# Sheet1.net
KiCad netlist of a schematic drawn in Altium Designer
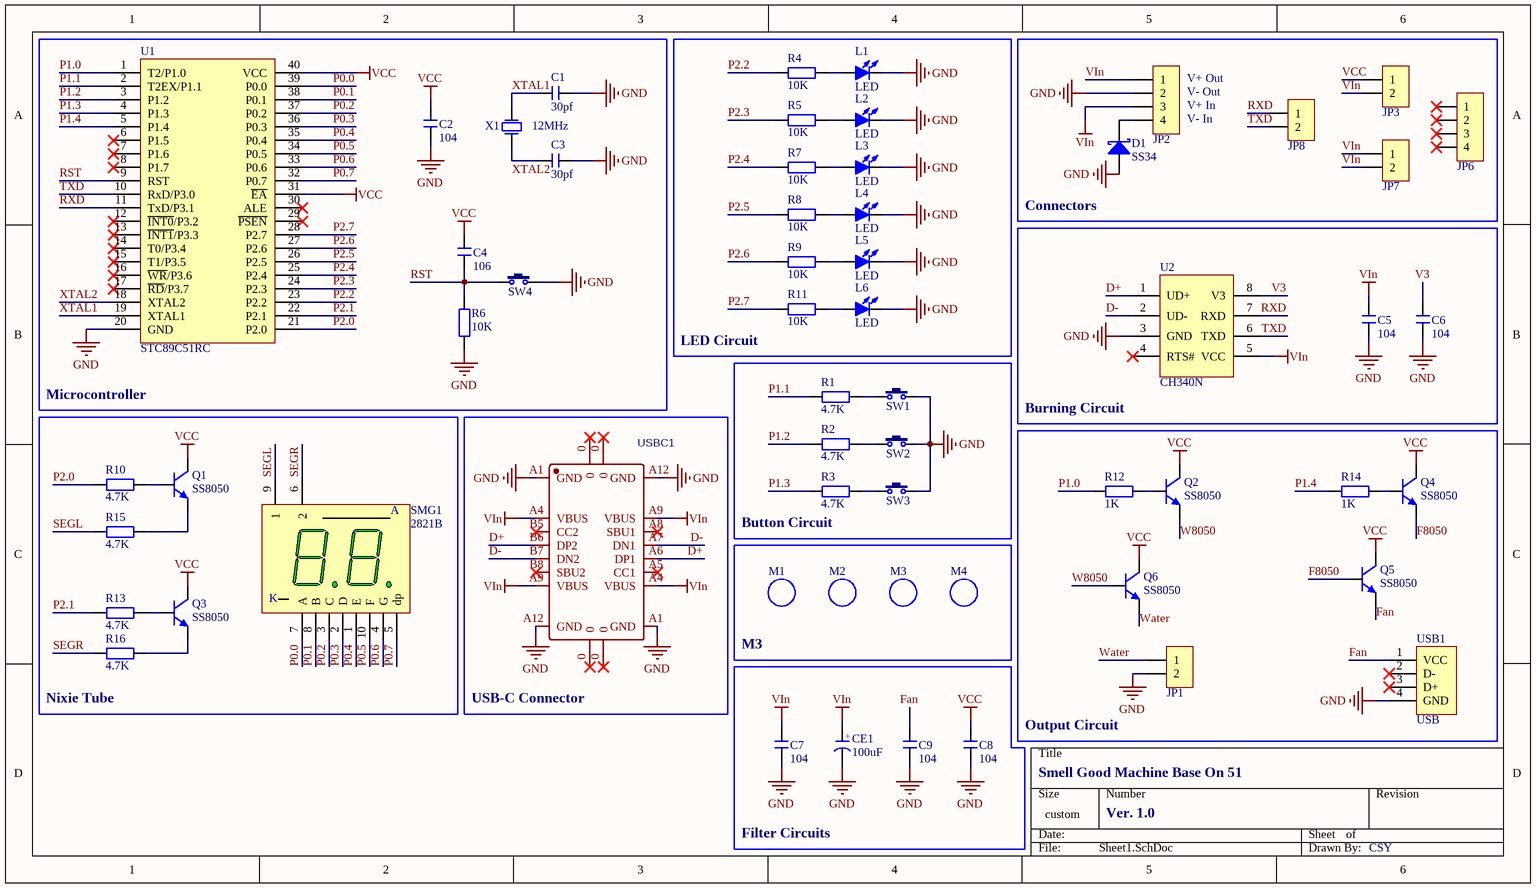
[diagram p0: Sheet1.SchDoc]

(export (version "E")
  (design (tool "Eeschema 10.0.6"))
  (components
    (comp (ref "C1")
      (value "30pf")
      (footprint "C 0805_M")
      (description "贴片电容")
      (libsource (lib "01 - 电容-电阻-电感") (part "C"))
    )
    (comp (ref "C2")
      (value "104")
      (footprint "C 0805_M")
      (description "贴片电容")
      (libsource (lib "01 - 电容-电阻-电感") (part "C"))
    )
    (comp (ref "C3")
      (value "30pf")
      (footprint "C 0805_M")
      (description "贴片电容")
      (libsource (lib "01 - 电容-电阻-电感") (part "C"))
    )
    (comp (ref "C4")
      (value "106")
      (footprint "C 0805_M")
      (description "贴片电容")
      (libsource (lib "01 - 电容-电阻-电感") (part "C"))
    )
    (comp (ref "C5")
      (value "104")
      (footprint "C 0805_M")
      (description "贴片电容")
      (libsource (lib "01 - 电容-电阻-电感") (part "C"))
    )
    (comp (ref "C6")
      (value "104")
      (footprint "C 0805_M")
      (description "贴片电容")
      (libsource (lib "01 - 电容-电阻-电感") (part "C"))
    )
    (comp (ref "C7")
      (value "104")
      (footprint "C 0805_M")
      (description "贴片电容")
      (libsource (lib "01 - 电容-电阻-电感") (part "C"))
    )
    (comp (ref "C8")
      (value "104")
      (footprint "C 0805_M")
      (description "贴片电容")
      (libsource (lib "01 - 电容-电阻-电感") (part "C"))
    )
    (comp (ref "C9")
      (value "104")
      (footprint "C 0805_M")
      (description "贴片电容")
      (libsource (lib "01 - 电容-电阻-电感") (part "C"))
    )
    (comp (ref "CE1")
      (value "100uF")
      (footprint "CM D(6.3*7.7)")
      (description "贴片电解电容")
      (libsource (lib "01 - 电容-电阻-电感") (part "CE_SMD"))
    )
    (comp (ref "D1")
      (value "SS34")
      (footprint "SMA")
      (description "肖特基二极管")
      (libsource (lib "02 - 二极管(LED)-三极管-整流桥") (part "SS34"))
    )
    (comp (ref "JP1")
      (value "HDR-1X2")
      (footprint "HDR2.54-LI-2P")
      (description "2P接插件")
      (libsource (lib "17 - 接插件-脚距2.54mm (100mil) ") (part "Header 2"))
    )
    (comp (ref "JP2")
      (value "HDR-1X4")
      (footprint "HDR2.54-LI-4P")
      (description "4P接插件")
      (libsource (lib "17 - 接插件-脚距2.54mm (100mil) ") (part "Header 4"))
    )
    (comp (ref "JP3")
      (value "HDR-1X2")
      (footprint "HDR2.54-LI-2P")
      (description "2P接插件")
      (libsource (lib "17 - 接插件-脚距2.54mm (100mil) ") (part "Header 2"))
    )
    (comp (ref "JP6")
      (value "HDR-1X4")
      (footprint "HDR2.54-LI-4P")
      (description "4P接插件")
      (libsource (lib "17 - 接插件-脚距2.54mm (100mil) ") (part "Header 4"))
    )
    (comp (ref "JP7")
      (value "HDR-1X2")
      (footprint "HDR2.54-LI-2P")
      (description "2P接插件")
      (libsource (lib "17 - 接插件-脚距2.54mm (100mil) ") (part "Header 2"))
    )
    (comp (ref "JP8")
      (value "HDR-1X2")
      (footprint "HDR2.54-LI-2P")
      (description "2P接插件")
      (libsource (lib "17 - 接插件-脚距2.54mm (100mil) ") (part "Header 2"))
    )
    (comp (ref "L1")
      (value "LED")
      (footprint "LED 0805B")
      (description "发光二极管")
      (libsource (lib "02 - 二极管(LED)-三极管-整流桥") (part "LED"))
    )
    (comp (ref "L2")
      (value "LED")
      (footprint "LED 0805R")
      (description "发光二极管")
      (libsource (lib "02 - 二极管(LED)-三极管-整流桥") (part "LED"))
    )
    (comp (ref "L3")
      (value "LED")
      (footprint "LED 0805R")
      (description "发光二极管")
      (libsource (lib "02 - 二极管(LED)-三极管-整流桥") (part "LED"))
    )
    (comp (ref "L4")
      (value "LED")
      (footprint "LED 0805R")
      (description "发光二极管")
      (libsource (lib "02 - 二极管(LED)-三极管-整流桥") (part "LED"))
    )
    (comp (ref "L5")
      (value "LED")
      (footprint "LED 0805R")
      (description "发光二极管")
      (libsource (lib "02 - 二极管(LED)-三极管-整流桥") (part "LED"))
    )
    (comp (ref "L6")
      (value "LED")
      (footprint "LED 0805G")
      (description "发光二极管")
      (libsource (lib "02 - 二极管(LED)-三极管-整流桥") (part "LED"))
    )
    (comp (ref "M1")
      (value "M3")
      (footprint "M3x20_N")
      (description "铜柱孔")
      (libsource (lib "10 - 未分类元器件") (part "M3"))
    )
    (comp (ref "M2")
      (value "M3")
      (footprint "M3x20_N")
      (description "铜柱孔")
      (libsource (lib "10 - 未分类元器件") (part "M3"))
    )
    (comp (ref "M3")
      (value "M3")
      (footprint "M3x20_N")
      (description "铜柱孔")
      (libsource (lib "10 - 未分类元器件") (part "M3"))
    )
    (comp (ref "M4")
      (value "M3")
      (footprint "M3x20_N")
      (description "铜柱孔")
      (libsource (lib "10 - 未分类元器件") (part "M3"))
    )
    (comp (ref "Q1")
      (value "SS8050")
      (footprint "SOT23-3M")
      (description "高频放大-NPN型")
      (libsource (lib "02 - 二极管(LED)-三极管-整流桥") (part "8050-SMD"))
    )
    (comp (ref "Q2")
      (value "SS8050")
      (footprint "SOT23-3M")
      (description "高频放大-NPN型")
      (libsource (lib "02 - 二极管(LED)-三极管-整流桥") (part "8050-SMD"))
    )
    (comp (ref "Q3")
      (value "SS8050")
      (footprint "SOT23-3M")
      (description "高频放大-NPN型")
      (libsource (lib "02 - 二极管(LED)-三极管-整流桥") (part "8050-SMD"))
    )
    (comp (ref "Q4")
      (value "SS8050")
      (footprint "SOT23-3M")
      (description "高频放大-NPN型")
      (libsource (lib "02 - 二极管(LED)-三极管-整流桥") (part "8050-SMD"))
    )
    (comp (ref "Q5")
      (value "SS8050")
      (footprint "SOT23-3M")
      (description "高频放大-NPN型")
      (libsource (lib "02 - 二极管(LED)-三极管-整流桥") (part "8050-SMD"))
    )
    (comp (ref "Q6")
      (value "SS8050")
      (footprint "SOT23-3M")
      (description "高频放大-NPN型")
      (libsource (lib "02 - 二极管(LED)-三极管-整流桥") (part "8050-SMD"))
    )
    (comp (ref "R1")
      (value "4.7K")
      (footprint "R 0805_M")
      (description "贴片电阻")
      (libsource (lib "01 - 电容-电阻-电感") (part "R"))
    )
    (comp (ref "R2")
      (value "4.7K")
      (footprint "R 0805_M")
      (description "贴片电阻")
      (libsource (lib "01 - 电容-电阻-电感") (part "R"))
    )
    (comp (ref "R3")
      (value "4.7K")
      (footprint "R 0805_M")
      (description "贴片电阻")
      (libsource (lib "01 - 电容-电阻-电感") (part "R"))
    )
    (comp (ref "R4")
      (value "10K")
      (footprint "R 0805_M")
      (description "贴片电阻")
      (libsource (lib "01 - 电容-电阻-电感") (part "R"))
    )
    (comp (ref "R5")
      (value "10K")
      (footprint "R 0805_M")
      (description "贴片电阻")
      (libsource (lib "01 - 电容-电阻-电感") (part "R"))
    )
    (comp (ref "R6")
      (value "10K")
      (footprint "R 0805_M")
      (description "贴片电阻")
      (libsource (lib "01 - 电容-电阻-电感") (part "R"))
    )
    (comp (ref "R7")
      (value "10K")
      (footprint "R 0805_M")
      (description "贴片电阻")
      (libsource (lib "01 - 电容-电阻-电感") (part "R"))
    )
    (comp (ref "R8")
      (value "10K")
      (footprint "R 0805_M")
      (description "贴片电阻")
      (libsource (lib "01 - 电容-电阻-电感") (part "R"))
    )
    (comp (ref "R9")
      (value "10K")
      (footprint "R 0805_M")
      (description "贴片电阻")
      (libsource (lib "01 - 电容-电阻-电感") (part "R"))
    )
    (comp (ref "R10")
      (value "4.7K")
      (footprint "R 0805_M")
      (description "贴片电阻")
      (libsource (lib "01 - 电容-电阻-电感") (part "R"))
    )
    (comp (ref "R11")
      (value "10K")
      (footprint "R 0805_M")
      (description "贴片电阻")
      (libsource (lib "01 - 电容-电阻-电感") (part "R"))
    )
    (comp (ref "R12")
      (value "1K")
      (footprint "R 0805_M")
      (description "贴片电阻")
      (libsource (lib "01 - 电容-电阻-电感") (part "R"))
    )
    (comp (ref "R13")
      (value "4.7K")
      (footprint "R 0805_M")
      (description "贴片电阻")
      (libsource (lib "01 - 电容-电阻-电感") (part "R"))
    )
    (comp (ref "R14")
      (value "1K")
      (footprint "R 0805_M")
      (description "贴片电阻")
      (libsource (lib "01 - 电容-电阻-电感") (part "R"))
    )
    (comp (ref "R15")
      (value "4.7K")
      (footprint "R 0805_M")
      (description "贴片电阻")
      (libsource (lib "01 - 电容-电阻-电感") (part "R"))
    )
    (comp (ref "R16")
      (value "4.7K")
      (footprint "R 0805_M")
      (description "贴片电阻")
      (libsource (lib "01 - 电容-电阻-电感") (part "R"))
    )
    (comp (ref "SMG1")
      (value "2821B")
      (footprint "SMG 0.28-2P")
      (description "0.28寸2位共阳数码管")
      (libsource (lib "05 - 点阵-液晶-数码管-TFT") (part "2821B"))
    )
    (comp (ref "SW1")
      (value "3x6x5")
      (footprint "TSW SMD-3*6*2.5")
      (description "3x6轻触开关")
      (libsource (lib "03 - 按键-开关-晶振-蜂鸣器") (part "TSW 3x6"))
    )
    (comp (ref "SW2")
      (value "3x6x5")
      (footprint "TSW SMD-3*6*2.5")
      (description "3x6轻触开关")
      (libsource (lib "03 - 按键-开关-晶振-蜂鸣器") (part "TSW 3x6"))
    )
    (comp (ref "SW3")
      (value "3x6x5")
      (footprint "TSW SMD-3*6*2.5")
      (description "3x6轻触开关")
      (libsource (lib "03 - 按键-开关-晶振-蜂鸣器") (part "TSW 3x6"))
    )
    (comp (ref "SW4")
      (value "3x6x5")
      (footprint "TSW SMD-3*6*2.5")
      (description "3x6轻触开关")
      (libsource (lib "03 - 按键-开关-晶振-蜂鸣器") (part "TSW 3x6"))
    )
    (comp (ref "U1")
      (value "STC89C51RC")
      (footprint "DIP40-600_MH")
      (description "STC单片机")
      (libsource (lib "25 - STC系列单片机") (part "STC89C51RC"))
    )
    (comp (ref "U2")
      (value "CH340N")
      (footprint "SOP8_M")
      (description "CH340N/CH330N")
      (libsource (lib "Schlib1") (part "CH340N"))
    )
    (comp (ref "USB1")
      (value "USB")
      (footprint "USB-A/S_D")
      (description "USB-A型母接口")
      (libsource (lib "04 - 接口类-USB接口-网口") (part "USB-A/S"))
    )
    (comp (ref "USBC1")
      (value "TYPE-C-31-M-12")
      (footprint "USB-TYPE-C-R")
      (description "Type-C母座")
      (fields (field (name "BOM_SUPPLIER PART") "C165948") (field (name "CONTRIBUTOR") "LCSC"))
      (libsource (lib "Schlib1") (part "TYPE-C-31-M-12"))
    )
    (comp (ref "X1")
      (value "12MHz")
      (footprint "OSC HC-49SMD")
      (description "2脚无源脚晶振")
      (libsource (lib "03 - 按键-开关-晶振-蜂鸣器") (part "XTAL-2P"))
    )
  )
  (nets
    (net (code "1") (name "/D+") (class "Default")
      (node (ref "U2") (pin "1") (pinfunction "UD+_1") (pintype "passive"))
      (node (ref "USBC1") (pin "A6") (pinfunction "DP1_A6") (pintype "passive"))
      (node (ref "USBC1") (pin "B6") (pinfunction "DP2_B6") (pintype "passive"))
    )
    (net (code "2") (name "/D-") (class "Default")
      (node (ref "U2") (pin "2") (pinfunction "UD-_2") (pintype "passive"))
      (node (ref "USBC1") (pin "A7") (pinfunction "DN1_A7") (pintype "passive"))
      (node (ref "USBC1") (pin "B7") (pinfunction "DN2_B7") (pintype "passive"))
    )
    (net (code "3") (name "/F8050") (class "Default")
      (node (ref "Q4") (pin "2") (pinfunction "E_2") (pintype "passive"))
      (node (ref "Q5") (pin "1") (pinfunction "B_1") (pintype "passive"))
    )
    (net (code "4") (name "/Fan") (class "Default")
      (node (ref "C9") (pin "2") (pinfunction "2_2") (pintype "passive"))
      (node (ref "Q5") (pin "2") (pinfunction "E_2") (pintype "passive"))
      (node (ref "USB1") (pin "1") (pinfunction "VCC_1") (pintype "passive"))
    )
    (net (code "5") (name "/P0.0") (class "Default")
      (node (ref "SMG1") (pin "7") (pinfunction "A_7") (pintype "passive"))
      (node (ref "U1") (pin "39") (pinfunction "P0.0_39") (pintype "passive"))
    )
    (net (code "6") (name "/P0.1") (class "Default")
      (node (ref "SMG1") (pin "8") (pinfunction "B_8") (pintype "passive"))
      (node (ref "U1") (pin "38") (pinfunction "P0.1_38") (pintype "passive"))
    )
    (net (code "7") (name "/P0.2") (class "Default")
      (node (ref "SMG1") (pin "3") (pinfunction "C_3") (pintype "passive"))
      (node (ref "U1") (pin "37") (pinfunction "P0.2_37") (pintype "passive"))
    )
    (net (code "8") (name "/P0.3") (class "Default")
      (node (ref "SMG1") (pin "2") (pinfunction "D_2") (pintype "passive"))
      (node (ref "U1") (pin "36") (pinfunction "P0.3_36") (pintype "passive"))
    )
    (net (code "9") (name "/P0.4") (class "Default")
      (node (ref "SMG1") (pin "1") (pinfunction "E_1") (pintype "passive"))
      (node (ref "U1") (pin "35") (pinfunction "P0.4_35") (pintype "passive"))
    )
    (net (code "10") (name "/P0.5") (class "Default")
      (node (ref "SMG1") (pin "10") (pinfunction "F_10") (pintype "passive"))
      (node (ref "U1") (pin "34") (pinfunction "P0.5_34") (pintype "passive"))
    )
    (net (code "11") (name "/P0.6") (class "Default")
      (node (ref "SMG1") (pin "4") (pinfunction "G_4") (pintype "passive"))
      (node (ref "U1") (pin "33") (pinfunction "P0.6_33") (pintype "passive"))
    )
    (net (code "12") (name "/P0.7") (class "Default")
      (node (ref "SMG1") (pin "5") (pinfunction "dp_5") (pintype "passive"))
      (node (ref "U1") (pin "32") (pinfunction "P0.7_32") (pintype "passive"))
    )
    (net (code "13") (name "/P1.0") (class "Default")
      (node (ref "R12") (pin "2") (pinfunction "2_2") (pintype "passive"))
      (node (ref "U1") (pin "1") (pinfunction "T2/P1.0_1") (pintype "passive"))
    )
    (net (code "14") (name "/P1.1") (class "Default")
      (node (ref "R1") (pin "2") (pinfunction "2_2") (pintype "passive"))
      (node (ref "U1") (pin "2") (pinfunction "T2EX/P1.1_2") (pintype "passive"))
    )
    (net (code "15") (name "/P1.2") (class "Default")
      (node (ref "R2") (pin "2") (pinfunction "2_2") (pintype "passive"))
      (node (ref "U1") (pin "3") (pinfunction "P1.2_3") (pintype "passive"))
    )
    (net (code "16") (name "/P1.3") (class "Default")
      (node (ref "R3") (pin "2") (pinfunction "2_2") (pintype "passive"))
      (node (ref "U1") (pin "4") (pinfunction "P1.3_4") (pintype "passive"))
    )
    (net (code "17") (name "/P1.4") (class "Default")
      (node (ref "R14") (pin "2") (pinfunction "2_2") (pintype "passive"))
      (node (ref "U1") (pin "5") (pinfunction "P1.4_5") (pintype "passive"))
    )
    (net (code "18") (name "/P2.0") (class "Default")
      (node (ref "R10") (pin "2") (pinfunction "2_2") (pintype "passive"))
      (node (ref "U1") (pin "21") (pinfunction "P2.0_21") (pintype "passive"))
    )
    (net (code "19") (name "/P2.1") (class "Default")
      (node (ref "R13") (pin "2") (pinfunction "2_2") (pintype "passive"))
      (node (ref "U1") (pin "22") (pinfunction "P2.1_22") (pintype "passive"))
    )
    (net (code "20") (name "/P2.2") (class "Default")
      (node (ref "R4") (pin "2") (pinfunction "2_2") (pintype "passive"))
      (node (ref "U1") (pin "23") (pinfunction "P2.2_23") (pintype "passive"))
    )
    (net (code "21") (name "/P2.3") (class "Default")
      (node (ref "R5") (pin "2") (pinfunction "2_2") (pintype "passive"))
      (node (ref "U1") (pin "24") (pinfunction "P2.3_24") (pintype "passive"))
    )
    (net (code "22") (name "/P2.4") (class "Default")
      (node (ref "R7") (pin "2") (pinfunction "2_2") (pintype "passive"))
      (node (ref "U1") (pin "25") (pinfunction "P2.4_25") (pintype "passive"))
    )
    (net (code "23") (name "/P2.5") (class "Default")
      (node (ref "R8") (pin "2") (pinfunction "2_2") (pintype "passive"))
      (node (ref "U1") (pin "26") (pinfunction "P2.5_26") (pintype "passive"))
    )
    (net (code "24") (name "/P2.6") (class "Default")
      (node (ref "R9") (pin "2") (pinfunction "2_2") (pintype "passive"))
      (node (ref "U1") (pin "27") (pinfunction "P2.6_27") (pintype "passive"))
    )
    (net (code "25") (name "/P2.7") (class "Default")
      (node (ref "R11") (pin "2") (pinfunction "2_2") (pintype "passive"))
      (node (ref "U1") (pin "28") (pinfunction "P2.7_28") (pintype "passive"))
    )
    (net (code "26") (name "/RST") (class "Default")
      (node (ref "C4") (pin "1") (pinfunction "1_1") (pintype "passive"))
      (node (ref "R6") (pin "2") (pinfunction "2_2") (pintype "passive"))
      (node (ref "SW4") (pin "1") (pinfunction "1_1") (pintype "passive"))
      (node (ref "U1") (pin "9") (pinfunction "RST_9") (pintype "passive"))
    )
    (net (code "27") (name "/RXD") (class "Default")
      (node (ref "JP8") (pin "1") (pinfunction "1_1") (pintype "passive"))
      (node (ref "U1") (pin "11") (pinfunction "TxD/P3.1_11") (pintype "passive"))
      (node (ref "U2") (pin "7") (pinfunction "RXD_7") (pintype "passive"))
    )
    (net (code "28") (name "/SEGL") (class "Default")
      (node (ref "R15") (pin "2") (pinfunction "2_2") (pintype "passive"))
      (node (ref "SMG1") (pin "9") (pinfunction "1_9") (pintype "passive"))
    )
    (net (code "29") (name "/SEGR") (class "Default")
      (node (ref "R16") (pin "2") (pinfunction "2_2") (pintype "passive"))
      (node (ref "SMG1") (pin "6") (pinfunction "2_6") (pintype "passive"))
    )
    (net (code "30") (name "/TXD") (class "Default")
      (node (ref "JP8") (pin "2") (pinfunction "2_2") (pintype "passive"))
      (node (ref "U1") (pin "10") (pinfunction "RxD/P3.0_10") (pintype "passive"))
      (node (ref "U2") (pin "6") (pinfunction "TXD_6") (pintype "passive"))
    )
    (net (code "31") (name "/V3") (class "Default")
      (node (ref "C6") (pin "2") (pinfunction "2_2") (pintype "passive"))
      (node (ref "U2") (pin "8") (pinfunction "V3_8") (pintype "passive"))
    )
    (net (code "32") (name "/W8050") (class "Default")
      (node (ref "Q2") (pin "2") (pinfunction "E_2") (pintype "passive"))
      (node (ref "Q6") (pin "1") (pinfunction "B_1") (pintype "passive"))
    )
    (net (code "33") (name "/Water") (class "Default")
      (node (ref "JP1") (pin "1") (pinfunction "1_1") (pintype "passive"))
      (node (ref "Q6") (pin "2") (pinfunction "E_2") (pintype "passive"))
    )
    (net (code "34") (name "/XTAL1") (class "Default")
      (node (ref "C1") (pin "1") (pinfunction "1_1") (pintype "passive"))
      (node (ref "U1") (pin "19") (pinfunction "XTAL1_19") (pintype "passive"))
      (node (ref "X1") (pin "2") (pinfunction "2_2") (pintype "passive"))
    )
    (net (code "35") (name "/XTAL2") (class "Default")
      (node (ref "C3") (pin "1") (pinfunction "1_1") (pintype "passive"))
      (node (ref "U1") (pin "18") (pinfunction "XTAL2_18") (pintype "passive"))
      (node (ref "X1") (pin "1") (pinfunction "1_1") (pintype "passive"))
    )
    (net (code "36") (name "GND") (class "Default")
      (node (ref "C1") (pin "2") (pinfunction "2_2") (pintype "passive"))
      (node (ref "C2") (pin "1") (pinfunction "1_1") (pintype "passive"))
      (node (ref "C3") (pin "2") (pinfunction "2_2") (pintype "passive"))
      (node (ref "C5") (pin "1") (pinfunction "1_1") (pintype "passive"))
      (node (ref "C6") (pin "1") (pinfunction "1_1") (pintype "passive"))
      (node (ref "C7") (pin "1") (pinfunction "1_1") (pintype "passive"))
      (node (ref "C8") (pin "1") (pinfunction "1_1") (pintype "passive"))
      (node (ref "C9") (pin "1") (pinfunction "1_1") (pintype "passive"))
      (node (ref "CE1") (pin "2") (pinfunction "K_2") (pintype "passive"))
      (node (ref "D1") (pin "1") (pinfunction "A_1") (pintype "passive"))
      (node (ref "JP1") (pin "2") (pinfunction "2_2") (pintype "passive"))
      (node (ref "JP2") (pin "2") (pinfunction "2_2") (pintype "passive"))
      (node (ref "L1") (pin "2") (pinfunction "K_2") (pintype "passive"))
      (node (ref "L2") (pin "2") (pinfunction "K_2") (pintype "passive"))
      (node (ref "L3") (pin "2") (pinfunction "K_2") (pintype "passive"))
      (node (ref "L4") (pin "2") (pinfunction "K_2") (pintype "passive"))
      (node (ref "L5") (pin "2") (pinfunction "K_2") (pintype "passive"))
      (node (ref "L6") (pin "2") (pinfunction "K_2") (pintype "passive"))
      (node (ref "R6") (pin "1") (pinfunction "1_1") (pintype "passive"))
      (node (ref "SW1") (pin "2") (pinfunction "2_2") (pintype "passive"))
      (node (ref "SW2") (pin "2") (pinfunction "2_2") (pintype "passive"))
      (node (ref "SW3") (pin "2") (pinfunction "2_2") (pintype "passive"))
      (node (ref "SW4") (pin "2") (pinfunction "2_2") (pintype "passive"))
      (node (ref "U1") (pin "20") (pinfunction "GND_20") (pintype "passive"))
      (node (ref "U2") (pin "3") (pinfunction "GND_3") (pintype "passive"))
      (node (ref "USB1") (pin "4") (pinfunction "GND_4") (pintype "passive"))
      (node (ref "USBC1") (pin "A1") (pinfunction "GND_A1") (pintype "passive"))
      (node (ref "USBC1") (pin "A12") (pinfunction "GND_A12") (pintype "passive"))
    )
    (net (code "37") (name "Net-(D1-K)") (class "Default")
      (node (ref "D1") (pin "2") (pinfunction "K_2") (pintype "passive"))
      (node (ref "JP2") (pin "4") (pinfunction "4_4") (pintype "passive"))
    )
    (net (code "38") (name "Net-(L1-A)") (class "Default")
      (node (ref "L1") (pin "1") (pinfunction "A_1") (pintype "passive"))
      (node (ref "R4") (pin "1") (pinfunction "1_1") (pintype "passive"))
    )
    (net (code "39") (name "Net-(L2-A)") (class "Default")
      (node (ref "L2") (pin "1") (pinfunction "A_1") (pintype "passive"))
      (node (ref "R5") (pin "1") (pinfunction "1_1") (pintype "passive"))
    )
    (net (code "40") (name "Net-(L3-A)") (class "Default")
      (node (ref "L3") (pin "1") (pinfunction "A_1") (pintype "passive"))
      (node (ref "R7") (pin "1") (pinfunction "1_1") (pintype "passive"))
    )
    (net (code "41") (name "Net-(L4-A)") (class "Default")
      (node (ref "L4") (pin "1") (pinfunction "A_1") (pintype "passive"))
      (node (ref "R8") (pin "1") (pinfunction "1_1") (pintype "passive"))
    )
    (net (code "42") (name "Net-(L5-A)") (class "Default")
      (node (ref "L5") (pin "1") (pinfunction "A_1") (pintype "passive"))
      (node (ref "R9") (pin "1") (pinfunction "1_1") (pintype "passive"))
    )
    (net (code "43") (name "Net-(L6-A)") (class "Default")
      (node (ref "L6") (pin "1") (pinfunction "A_1") (pintype "passive"))
      (node (ref "R11") (pin "1") (pinfunction "1_1") (pintype "passive"))
    )
    (net (code "44") (name "Net-(Q1-B)") (class "Default")
      (node (ref "Q1") (pin "1") (pinfunction "B_1") (pintype "passive"))
      (node (ref "R10") (pin "1") (pinfunction "1_1") (pintype "passive"))
    )
    (net (code "45") (name "Net-(Q1-E)") (class "Default")
      (node (ref "Q1") (pin "2") (pinfunction "E_2") (pintype "passive"))
      (node (ref "R15") (pin "1") (pinfunction "1_1") (pintype "passive"))
    )
    (net (code "46") (name "Net-(Q2-B)") (class "Default")
      (node (ref "Q2") (pin "1") (pinfunction "B_1") (pintype "passive"))
      (node (ref "R12") (pin "1") (pinfunction "1_1") (pintype "passive"))
    )
    (net (code "47") (name "Net-(Q3-B)") (class "Default")
      (node (ref "Q3") (pin "1") (pinfunction "B_1") (pintype "passive"))
      (node (ref "R13") (pin "1") (pinfunction "1_1") (pintype "passive"))
    )
    (net (code "48") (name "Net-(Q3-E)") (class "Default")
      (node (ref "Q3") (pin "2") (pinfunction "E_2") (pintype "passive"))
      (node (ref "R16") (pin "1") (pinfunction "1_1") (pintype "passive"))
    )
    (net (code "49") (name "Net-(Q4-B)") (class "Default")
      (node (ref "Q4") (pin "1") (pinfunction "B_1") (pintype "passive"))
      (node (ref "R14") (pin "1") (pinfunction "1_1") (pintype "passive"))
    )
    (net (code "50") (name "Net-(R1-Pad1)") (class "Default")
      (node (ref "R1") (pin "1") (pinfunction "1_1") (pintype "passive"))
      (node (ref "SW1") (pin "1") (pinfunction "1_1") (pintype "passive"))
    )
    (net (code "51") (name "Net-(R2-Pad1)") (class "Default")
      (node (ref "R2") (pin "1") (pinfunction "1_1") (pintype "passive"))
      (node (ref "SW2") (pin "1") (pinfunction "1_1") (pintype "passive"))
    )
    (net (code "52") (name "Net-(R3-Pad1)") (class "Default")
      (node (ref "R3") (pin "1") (pinfunction "1_1") (pintype "passive"))
      (node (ref "SW3") (pin "1") (pinfunction "1_1") (pintype "passive"))
    )
    (net (code "53") (name "VCC") (class "Default")
      (node (ref "C2") (pin "2") (pinfunction "2_2") (pintype "passive"))
      (node (ref "C4") (pin "2") (pinfunction "2_2") (pintype "passive"))
      (node (ref "C8") (pin "2") (pinfunction "2_2") (pintype "passive"))
      (node (ref "JP3") (pin "1") (pinfunction "1_1") (pintype "passive"))
      (node (ref "Q1") (pin "3") (pinfunction "C_3") (pintype "passive"))
      (node (ref "Q2") (pin "3") (pinfunction "C_3") (pintype "passive"))
      (node (ref "Q3") (pin "3") (pinfunction "C_3") (pintype "passive"))
      (node (ref "Q4") (pin "3") (pinfunction "C_3") (pintype "passive"))
      (node (ref "Q5") (pin "3") (pinfunction "C_3") (pintype "passive"))
      (node (ref "Q6") (pin "3") (pinfunction "C_3") (pintype "passive"))
      (node (ref "U1") (pin "31") (pinfunction "~{EA}_31") (pintype "passive"))
      (node (ref "U1") (pin "40") (pinfunction "VCC_40") (pintype "passive"))
    )
    (net (code "54") (name "VIn") (class "Default")
      (node (ref "C5") (pin "2") (pinfunction "2_2") (pintype "passive"))
      (node (ref "C7") (pin "2") (pinfunction "2_2") (pintype "passive"))
      (node (ref "CE1") (pin "1") (pinfunction "A_1") (pintype "passive"))
      (node (ref "JP2") (pin "1") (pinfunction "1_1") (pintype "passive"))
      (node (ref "JP2") (pin "3") (pinfunction "3_3") (pintype "passive"))
      (node (ref "JP3") (pin "2") (pinfunction "2_2") (pintype "passive"))
      (node (ref "JP7") (pin "1") (pinfunction "1_1") (pintype "passive"))
      (node (ref "JP7") (pin "2") (pinfunction "2_2") (pintype "passive"))
      (node (ref "U2") (pin "5") (pinfunction "VCC_5") (pintype "passive"))
      (node (ref "USBC1") (pin "A4") (pinfunction "VBUS_A4") (pintype "passive"))
      (node (ref "USBC1") (pin "A9") (pinfunction "VBUS_A9") (pintype "passive"))
    )
    (net (code "55") (name "unconnected-(JP6-Pad1)") (class "Default")
      (node (ref "JP6") (pin "1") (pinfunction "1_1") (pintype "passive+no_connect"))
    )
    (net (code "56") (name "unconnected-(JP6-Pad2)") (class "Default")
      (node (ref "JP6") (pin "2") (pinfunction "2_2") (pintype "passive+no_connect"))
    )
    (net (code "57") (name "unconnected-(JP6-Pad3)") (class "Default")
      (node (ref "JP6") (pin "3") (pinfunction "3_3") (pintype "passive+no_connect"))
    )
    (net (code "58") (name "unconnected-(JP6-Pad4)") (class "Default")
      (node (ref "JP6") (pin "4") (pinfunction "4_4") (pintype "passive+no_connect"))
    )
    (net (code "59") (name "unconnected-(U1-ALE-Pad30)") (class "Default")
      (node (ref "U1") (pin "30") (pinfunction "ALE_30") (pintype "passive+no_connect"))
    )
    (net (code "60") (name "unconnected-(U1-P1.5-Pad6)") (class "Default")
      (node (ref "U1") (pin "6") (pinfunction "P1.5_6") (pintype "passive+no_connect"))
    )
    (net (code "61") (name "unconnected-(U1-P1.6-Pad7)") (class "Default")
      (node (ref "U1") (pin "7") (pinfunction "P1.6_7") (pintype "passive+no_connect"))
    )
    (net (code "62") (name "unconnected-(U1-P1.7-Pad8)") (class "Default")
      (node (ref "U1") (pin "8") (pinfunction "P1.7_8") (pintype "passive+no_connect"))
    )
    (net (code "63") (name "unconnected-(U1-T0{slash}P3.4-Pad14)") (class "Default")
      (node (ref "U1") (pin "14") (pinfunction "T0/P3.4_14") (pintype "passive+no_connect"))
    )
    (net (code "64") (name "unconnected-(U1-T1{slash}P3.5-Pad15)") (class "Default")
      (node (ref "U1") (pin "15") (pinfunction "T1/P3.5_15") (pintype "passive+no_connect"))
    )
    (net (code "65") (name "unconnected-(U1-~{INT0}{slash}P3.2-Pad12)") (class "Default")
      (node (ref "U1") (pin "12") (pinfunction "~{INT0}/P3.2_12") (pintype "passive+no_connect"))
    )
    (net (code "66") (name "unconnected-(U1-~{INT1}{slash}P3.3-Pad13)") (class "Default")
      (node (ref "U1") (pin "13") (pinfunction "~{INT1}/P3.3_13") (pintype "passive+no_connect"))
    )
    (net (code "67") (name "unconnected-(U1-~{PSEN}-Pad29)") (class "Default")
      (node (ref "U1") (pin "29") (pinfunction "~{PSEN}_29") (pintype "passive+no_connect"))
    )
    (net (code "68") (name "unconnected-(U1-~{RD}{slash}P3.7-Pad17)") (class "Default")
      (node (ref "U1") (pin "17") (pinfunction "~{RD}/P3.7_17") (pintype "passive+no_connect"))
    )
    (net (code "69") (name "unconnected-(U1-~{WR}{slash}P3.6-Pad16)") (class "Default")
      (node (ref "U1") (pin "16") (pinfunction "~{WR}/P3.6_16") (pintype "passive+no_connect"))
    )
    (net (code "70") (name "unconnected-(U2-RTS#-Pad4)") (class "Default")
      (node (ref "U2") (pin "4") (pinfunction "RTS#_4") (pintype "passive+no_connect"))
    )
    (net (code "71") (name "unconnected-(USB1-D+-Pad3)") (class "Default")
      (node (ref "USB1") (pin "3") (pinfunction "D+_3") (pintype "passive+no_connect"))
    )
    (net (code "72") (name "unconnected-(USB1-D--Pad2)") (class "Default")
      (node (ref "USB1") (pin "2") (pinfunction "D-_2") (pintype "passive+no_connect"))
    )
    (net (code "73") (name "unconnected-(USBC1-CC1-PadA5)") (class "Default")
      (node (ref "USBC1") (pin "A5") (pinfunction "CC1_A5") (pintype "passive+no_connect"))
    )
    (net (code "74") (name "unconnected-(USBC1-CC2-PadB5)") (class "Default")
      (node (ref "USBC1") (pin "B5") (pinfunction "CC2_B5") (pintype "passive+no_connect"))
    )
    (net (code "75") (name "unconnected-(USBC1-Pad0)") (class "Default")
      (node (ref "USBC1") (pin "0") (pinfunction "0_0") (pintype "passive+no_connect"))
    )
    (net (code "76") (name "unconnected-(USBC1-Pad0)_1") (class "Default")
      (node (ref "USBC1") (pin "0") (pinfunction "0_0") (pintype "passive+no_connect"))
    )
    (net (code "77") (name "unconnected-(USBC1-Pad0)_2") (class "Default")
      (node (ref "USBC1") (pin "0") (pinfunction "0_0") (pintype "passive+no_connect"))
    )
    (net (code "78") (name "unconnected-(USBC1-Pad0)_3") (class "Default")
      (node (ref "USBC1") (pin "0") (pinfunction "0_0") (pintype "passive+no_connect"))
    )
    (net (code "79") (name "unconnected-(USBC1-SBU1-PadA8)") (class "Default")
      (node (ref "USBC1") (pin "A8") (pinfunction "SBU1_A8") (pintype "passive+no_connect"))
    )
    (net (code "80") (name "unconnected-(USBC1-SBU2-PadB8)") (class "Default")
      (node (ref "USBC1") (pin "B8") (pinfunction "SBU2_B8") (pintype "passive+no_connect"))
    )
  )
)
